# SCH_SrProj_v1_3.net
KiCad netlist of a schematic drawn in EasyEDA
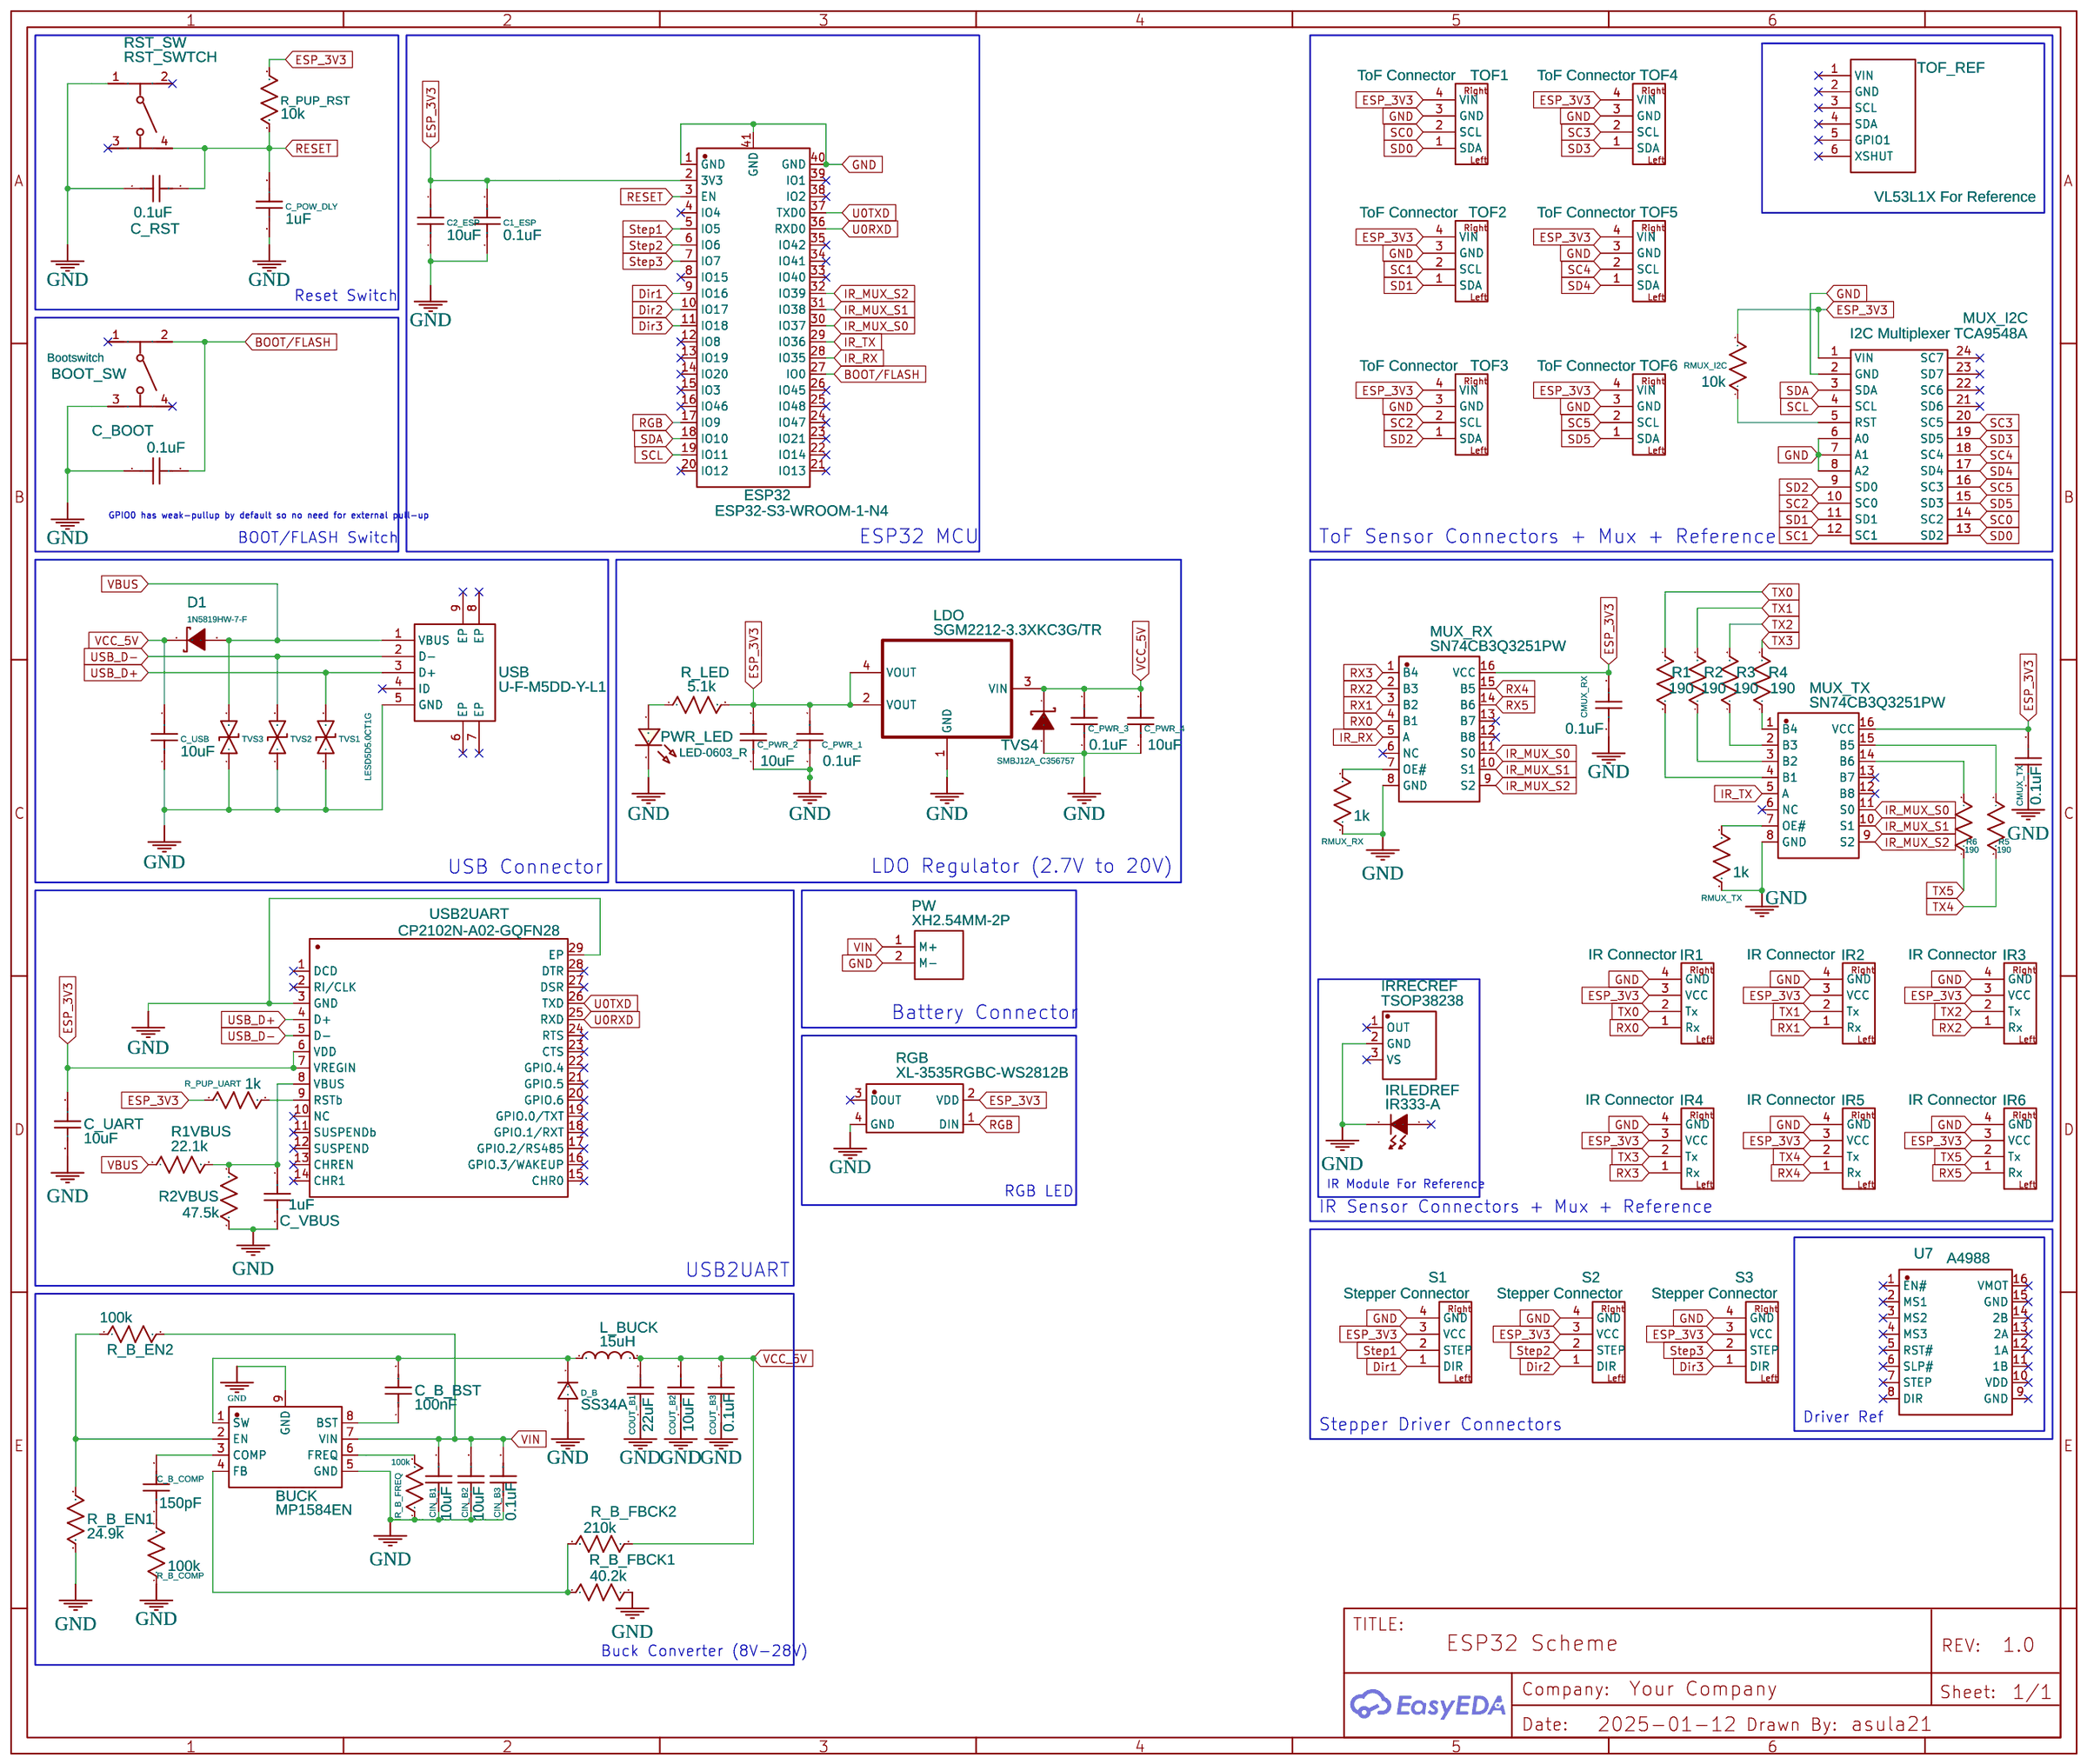
[diagram p0: schematic sheet]

(export (version "E")
  (design (tool "Eeschema 10.0.6"))
  (components
    (comp (ref "BOOT_SW")
      (value "Bootswitch")
      (fields
        (field (name "Manufacturer Part") "Switch,6*6*6Plastic head,260G, 0.25mm,Straight line")
        (field (name "Manufacturer") "BBJ")
      )
      (libsource (lib "") (part "Button-6x6x6mm_1"))
    )
    (comp (ref "BUCK") (value "MP1584EN") (libsource (lib "") (part "MP1584EN")))
    (comp (ref "C1_ESP") (value "0.1uF") (libsource (lib "") (part "C_0603_US")))
    (comp (ref "C2_ESP") (value "10uF") (libsource (lib "") (part "C_0603_US_14")))
    (comp (ref "CIN_B1") (value "10uF") (libsource (lib "") (part "C_0603_US_1")))
    (comp (ref "CIN_B2") (value "10uF") (libsource (lib "") (part "C_0603_US_1")))
    (comp (ref "CIN_B3") (value "0.1uF") (libsource (lib "") (part "C_0603_US_1")))
    (comp (ref "CMUX_RX") (value "0.1uF") (libsource (lib "") (part "C_0603_US_8")))
    (comp (ref "CMUX_TX") (value "0.1uF") (libsource (lib "") (part "C_0603_US_10")))
    (comp (ref "COUT_B1") (value "22uF") (libsource (lib "") (part "C_0603_US_3")))
    (comp (ref "COUT_B2") (value "10uF") (libsource (lib "") (part "C_0603_US_3")))
    (comp (ref "COUT_B3") (value "0.1uF") (libsource (lib "") (part "C_0603_US_3")))
    (comp (ref "C_BOOT") (value "0.1uF") (libsource (lib "") (part "C_0603_US_9")))
    (comp (ref "C_B_BST") (value "100nF") (libsource (lib "") (part "C_0603_US_12")))
    (comp (ref "C_B_COMP") (value "150pF") (libsource (lib "") (part "C_0603_US_13")))
    (comp (ref "C_POW_DLY") (value "1uF") (libsource (lib "") (part "C_0603_US_2")))
    (comp (ref "C_PWR_1") (value "0.1uF") (libsource (lib "") (part "C_0603_US_6")))
    (comp (ref "C_PWR_2") (value "10uF") (libsource (lib "") (part "C_0603_US_6")))
    (comp (ref "C_PWR_3") (value "0.1uF") (libsource (lib "") (part "C_0603_US_6")))
    (comp (ref "C_PWR_4") (value "10uF") (libsource (lib "") (part "C_0603_US_6")))
    (comp (ref "C_RST") (value "0.1uF") (libsource (lib "") (part "C_0603_US_7")))
    (comp (ref "C_UART") (value "10uF") (libsource (lib "") (part "C_0603_US_4")))
    (comp (ref "C_USB") (value "10uF") (libsource (lib "") (part "C_0603_US_5")))
    (comp (ref "C_VBUS") (value "1uF") (libsource (lib "") (part "C_0603_US_11")))
    (comp (ref "D1")
      (value "1N5819HW-7-F")
      (fields (field (name "Manufacturer") "DIODES(美台)"))
      (libsource (lib "") (part "1N5819HW-7-F"))
    )
    (comp (ref "D_B")
      (value "SS34A")
      (fields (field (name "Manufacturer") "YANGJIE(扬杰)"))
      (libsource (lib "") (part "SS34A"))
    )
    (comp (ref "ESP32")
      (value "ESP32-S3-WROOM-1-N4")
      (fields (field (name "Manufacturer") "ESPRESSIF(乐鑫)"))
      (libsource (lib "") (part "ESP32-S3-WROOM-1-N4"))
    )
    (comp (ref "IR1") (value "IR Connector") (libsource (lib "") (part "MY XH2.54MM.4P_1")))
    (comp (ref "IR2") (value "IR Connector") (libsource (lib "") (part "MY XH2.54MM.4P_1")))
    (comp (ref "IR3") (value "IR Connector") (libsource (lib "") (part "MY XH2.54MM.4P_1")))
    (comp (ref "IR4") (value "IR Connector") (libsource (lib "") (part "MY XH2.54MM.4P_1")))
    (comp (ref "IR5") (value "IR Connector") (libsource (lib "") (part "MY XH2.54MM.4P_1")))
    (comp (ref "IR6") (value "IR Connector") (libsource (lib "") (part "MY XH2.54MM.4P_1")))
    (comp (ref "IRLEDREF")
      (value "IR333-A")
      (fields (field (name "Manufacturer") "EVERLIGHT(亿光)"))
      (libsource (lib "") (part "IR333-A"))
    )
    (comp (ref "IRRECREF")
      (value "TSOP38238")
      (fields (field (name "Manufacturer") "VISHAY(威世)"))
      (libsource (lib "") (part "TSOP38238"))
    )
    (comp (ref "LDO") (value "SGM2212-3.3XKC3G/TR") (libsource (lib "") (part "SGM2212-3.3XKC3G/TR")))
    (comp (ref "L_BUCK")
      (value "15uH")
      (fields (field (name "Manufacturer Part") "CYH127-4.7UH") (field (name "Manufacturer") "SHOU HAN(首韩)"))
      (libsource (lib "") (part "CYH127-4.7UH"))
    )
    (comp (ref "MUX_I2C")
      (value "I2C Multiplexer TCA9548A")
      (fields (field (name "Manufacturer Part") "IDSN-TCA9548A") (field (name "Manufacturer") "IDSN"))
      (libsource (lib "") (part "TCA9548A I2C MULTIPLEXER 8 CHANEL"))
    )
    (comp (ref "MUX_RX")
      (value "SN74CB3Q3251PW")
      (fields (field (name "Manufacturer") "TI(德州仪器)"))
      (libsource (lib "") (part "SN74CB3Q3251PW"))
    )
    (comp (ref "MUX_TX")
      (value "SN74CB3Q3251PW")
      (fields (field (name "Manufacturer") "TI(德州仪器)"))
      (libsource (lib "") (part "SN74CB3Q3251PW_1"))
    )
    (comp (ref "PW")
      (value "XH2.54MM-2P")
      (fields (field (name "Manufacturer Part") "Header P2 PH2.0 TUANLE"))
      (libsource (lib "") (part "PH2.0-2P"))
    )
    (comp (ref "PWR_LED")
      (value "LED-0603_R")
      (fields
        (field (name "Manufacturer Part") "19-217/R6C-AL1M2VY/3T")
        (field (name "Manufacturer") "EVERLIGHT(台湾亿光)")
      )
      (libsource (lib "") (part "LED-0603_R"))
    )
    (comp (ref "R1") (value "190") (libsource (lib "") (part "R_0805_US_1")))
    (comp (ref "R1VBUS") (value "22.1k") (libsource (lib "") (part "R_0603_US_8")))
    (comp (ref "R2") (value "190") (libsource (lib "") (part "R_0805_US")))
    (comp (ref "R2VBUS") (value "47.5k") (libsource (lib "") (part "R_0603_US_11")))
    (comp (ref "R3") (value "190") (libsource (lib "") (part "R_0805_US")))
    (comp (ref "R4") (value "190") (libsource (lib "") (part "R_0805_US")))
    (comp (ref "R5") (value "190") (libsource (lib "") (part "R_0805_US_1")))
    (comp (ref "R6") (value "190") (libsource (lib "") (part "R_0805_US")))
    (comp (ref "RGB")
      (value "XL-3535RGBC-WS2812B")
      (fields (field (name "Manufacturer") "XINGLIGHT(成兴光)"))
      (libsource (lib "") (part "XL-3535RGBC-WS2812B"))
    )
    (comp (ref "RMUX_I2C") (value "10k") (libsource (lib "") (part "R_0603_US_1")))
    (comp (ref "RMUX_RX") (value "1k") (libsource (lib "") (part "R_0603_US_2")))
    (comp (ref "RMUX_TX") (value "1k") (libsource (lib "") (part "R_0603_US_3")))
    (comp (ref "RST_SW")
      (value "RST_SWTCH")
      (fields
        (field (name "Manufacturer Part") "Switch,6*6*6Plastic head,260G, 0.25mm,Straight line")
        (field (name "Manufacturer") "BBJ")
      )
      (libsource (lib "") (part "Button-6x6x6mm"))
    )
    (comp (ref "R_B_COMP") (value "100k") (libsource (lib "") (part "R_0603_US_4")))
    (comp (ref "R_B_EN1") (value "24.9k") (libsource (lib "") (part "R_0603_US_9")))
    (comp (ref "R_B_EN2") (value "100k") (libsource (lib "") (part "R_0603_US_7")))
    (comp (ref "R_B_FBCK1") (value "40.2k") (libsource (lib "") (part "R_0603_US")))
    (comp (ref "R_B_FBCK2") (value "210k") (libsource (lib "") (part "R_0603_US_13")))
    (comp (ref "R_B_FREQ") (value "100k") (libsource (lib "") (part "R_0603_US_12")))
    (comp (ref "R_LED") (value "5.1k") (libsource (lib "") (part "R_0603_US_5")))
    (comp (ref "R_PUP_RST") (value "10k") (libsource (lib "") (part "R_0603_US_6")))
    (comp (ref "R_PUP_UART") (value "1k") (libsource (lib "") (part "R_0603_US_10")))
    (comp (ref "S1") (value "Stepper Connector") (libsource (lib "") (part "MY XH2.54MM.4P_2")))
    (comp (ref "S2") (value "Stepper Connector") (libsource (lib "") (part "MY XH2.54MM.4P_2")))
    (comp (ref "S3") (value "Stepper Connector") (libsource (lib "") (part "MY XH2.54MM.4P_2")))
    (comp (ref "TOF1") (value "ToF Connector") (libsource (lib "") (part "MY XH2.54MM.4P")))
    (comp (ref "TOF2") (value "ToF Connector") (libsource (lib "") (part "MY XH2.54MM.4P")))
    (comp (ref "TOF3") (value "ToF Connector") (libsource (lib "") (part "MY XH2.54MM.4P")))
    (comp (ref "TOF4") (value "ToF Connector") (libsource (lib "") (part "MY XH2.54MM.4P")))
    (comp (ref "TOF5") (value "ToF Connector") (libsource (lib "") (part "MY XH2.54MM.4P")))
    (comp (ref "TOF6") (value "ToF Connector") (libsource (lib "") (part "MY XH2.54MM.4P")))
    (comp (ref "TOF_REF")
      (value "VL53L1X For Reference")
      (fields (field (name "Manufacturer Part") "VL53L0X Time-of-Flight Distance Sensor VL53L0X"))
      (libsource (lib "") (part "VL53L1X_BREAKOUT"))
    )
    (comp (ref "TVS1")
      (value "LESD5D5.0CT1G")
      (fields (field (name "Manufacturer") "LRC(乐山无线电)"))
      (libsource (lib "") (part "LESD5D5.0CT1G"))
    )
    (comp (ref "TVS2")
      (value "LESD5D5.0CT1G")
      (fields (field (name "Manufacturer") "LRC(乐山无线电)"))
      (libsource (lib "") (part "LESD5D5.0CT1G"))
    )
    (comp (ref "TVS3")
      (value "LESD5D5.0CT1G")
      (fields (field (name "Manufacturer") "LRC(乐山无线电)"))
      (libsource (lib "") (part "LESD5D5.0CT1G"))
    )
    (comp (ref "TVS4")
      (value "SMBJ12A_C356757")
      (fields (field (name "Manufacturer Part") "SMBJ12A") (field (name "Manufacturer") "JJW(捷捷微)"))
      (libsource (lib "") (part "SMBJ12A_C356757"))
    )
    (comp (ref "U7") (value "A4988") (libsource (lib "") (part "A4988")))
    (comp (ref "USB")
      (value "U-F-M5DD-Y-L1")
      (fields (field (name "Manufacturer") "韩国韩荣"))
      (libsource (lib "") (part "U-F-M5DD-Y-L1"))
    )
    (comp (ref "USB2UART")
      (value "CP2102N-A02-GQFN28")
      (fields (field (name "Manufacturer") "SKYWORKS/SILICON LABS(芯科)"))
      (libsource (lib "") (part "CP2102N-A02-GQFN28"))
    )
  )
  (nets
    (net (code "1") (name "BOOT{slash}FLASH") (class "Default")
      (node (ref "BOOT_SW") (pin "2") (pinfunction "2_2") (pintype "unspecified"))
      (node (ref "C_BOOT") (pin "2") (pinfunction "2_2") (pintype "unspecified"))
      (node (ref "ESP32") (pin "27") (pinfunction "IO0_27") (pintype "unspecified"))
    )
    (net (code "2") (name "Dir1") (class "Default")
      (node (ref "ESP32") (pin "9") (pinfunction "IO16_9") (pintype "unspecified"))
      (node (ref "S1") (pin "1") (pinfunction "DIR_1") (pintype "unspecified"))
    )
    (net (code "3") (name "Dir2") (class "Default")
      (node (ref "ESP32") (pin "10") (pinfunction "IO17_10") (pintype "unspecified"))
      (node (ref "S2") (pin "1") (pinfunction "DIR_1") (pintype "unspecified"))
    )
    (net (code "4") (name "Dir3") (class "Default")
      (node (ref "ESP32") (pin "11") (pinfunction "IO18_11") (pintype "unspecified"))
      (node (ref "S3") (pin "1") (pinfunction "DIR_1") (pintype "unspecified"))
    )
    (net (code "5") (name "ESP_3V3") (class "Default")
      (node (ref "C1_ESP") (pin "2") (pinfunction "2_2") (pintype "unspecified"))
      (node (ref "C2_ESP") (pin "2") (pinfunction "2_2") (pintype "unspecified"))
      (node (ref "CMUX_RX") (pin "2") (pinfunction "2_2") (pintype "unspecified"))
      (node (ref "CMUX_TX") (pin "2") (pinfunction "2_2") (pintype "unspecified"))
      (node (ref "C_PWR_1") (pin "2") (pinfunction "2_2") (pintype "unspecified"))
      (node (ref "C_PWR_2") (pin "2") (pinfunction "2_2") (pintype "unspecified"))
      (node (ref "C_UART") (pin "2") (pinfunction "2_2") (pintype "unspecified"))
      (node (ref "ESP32") (pin "2") (pinfunction "3V3_2") (pintype "unspecified"))
      (node (ref "IR1") (pin "3") (pinfunction "VCC_3") (pintype "unspecified"))
      (node (ref "IR2") (pin "3") (pinfunction "VCC_3") (pintype "unspecified"))
      (node (ref "IR3") (pin "3") (pinfunction "VCC_3") (pintype "unspecified"))
      (node (ref "IR4") (pin "3") (pinfunction "VCC_3") (pintype "unspecified"))
      (node (ref "IR5") (pin "3") (pinfunction "VCC_3") (pintype "unspecified"))
      (node (ref "IR6") (pin "3") (pinfunction "VCC_3") (pintype "unspecified"))
      (node (ref "LDO") (pin "2") (pinfunction "VOUT_2") (pintype "unspecified"))
      (node (ref "LDO") (pin "4") (pinfunction "VOUT_4") (pintype "unspecified"))
      (node (ref "MUX_I2C") (pin "1") (pinfunction "VIN_1") (pintype "unspecified"))
      (node (ref "MUX_RX") (pin "16") (pinfunction "VCC_16") (pintype "unspecified"))
      (node (ref "MUX_TX") (pin "16") (pinfunction "VCC_16") (pintype "unspecified"))
      (node (ref "RGB") (pin "2") (pinfunction "VDD_2") (pintype "unspecified"))
      (node (ref "RMUX_I2C") (pin "2") (pinfunction "2_2") (pintype "unspecified"))
      (node (ref "R_LED") (pin "2") (pinfunction "2_2") (pintype "unspecified"))
      (node (ref "R_PUP_RST") (pin "2") (pinfunction "2_2") (pintype "unspecified"))
      (node (ref "R_PUP_UART") (pin "2") (pinfunction "2_2") (pintype "unspecified"))
      (node (ref "S1") (pin "3") (pinfunction "VCC_3") (pintype "unspecified"))
      (node (ref "S2") (pin "3") (pinfunction "VCC_3") (pintype "unspecified"))
      (node (ref "S3") (pin "3") (pinfunction "VCC_3") (pintype "unspecified"))
      (node (ref "TOF1") (pin "4") (pinfunction "VIN_4") (pintype "unspecified"))
      (node (ref "TOF2") (pin "4") (pinfunction "VIN_4") (pintype "unspecified"))
      (node (ref "TOF3") (pin "4") (pinfunction "VIN_4") (pintype "unspecified"))
      (node (ref "TOF4") (pin "4") (pinfunction "VIN_4") (pintype "unspecified"))
      (node (ref "TOF5") (pin "4") (pinfunction "VIN_4") (pintype "unspecified"))
      (node (ref "TOF6") (pin "4") (pinfunction "VIN_4") (pintype "unspecified"))
      (node (ref "USB2UART") (pin "6") (pinfunction "VDD_6") (pintype "unspecified"))
      (node (ref "USB2UART") (pin "7") (pinfunction "VREGIN_7") (pintype "unspecified"))
    )
    (net (code "6") (name "GND") (class "Default")
      (node (ref "BOOT_SW") (pin "3") (pinfunction "3_3") (pintype "unspecified"))
      (node (ref "BUCK") (pin "5") (pinfunction "GND_5") (pintype "unspecified"))
      (node (ref "BUCK") (pin "9") (pinfunction "GND_9") (pintype "unspecified"))
      (node (ref "C1_ESP") (pin "1") (pinfunction "1_1") (pintype "unspecified"))
      (node (ref "C2_ESP") (pin "1") (pinfunction "1_1") (pintype "unspecified"))
      (node (ref "CIN_B1") (pin "1") (pinfunction "1_1") (pintype "unspecified"))
      (node (ref "CIN_B2") (pin "1") (pinfunction "1_1") (pintype "unspecified"))
      (node (ref "CIN_B3") (pin "1") (pinfunction "1_1") (pintype "unspecified"))
      (node (ref "CMUX_RX") (pin "1") (pinfunction "1_1") (pintype "unspecified"))
      (node (ref "CMUX_TX") (pin "1") (pinfunction "1_1") (pintype "unspecified"))
      (node (ref "COUT_B1") (pin "1") (pinfunction "1_1") (pintype "unspecified"))
      (node (ref "COUT_B2") (pin "1") (pinfunction "1_1") (pintype "unspecified"))
      (node (ref "COUT_B3") (pin "1") (pinfunction "1_1") (pintype "unspecified"))
      (node (ref "C_BOOT") (pin "1") (pinfunction "1_1") (pintype "unspecified"))
      (node (ref "C_POW_DLY") (pin "1") (pinfunction "1_1") (pintype "unspecified"))
      (node (ref "C_PWR_1") (pin "1") (pinfunction "1_1") (pintype "unspecified"))
      (node (ref "C_PWR_2") (pin "1") (pinfunction "1_1") (pintype "unspecified"))
      (node (ref "C_PWR_3") (pin "1") (pinfunction "1_1") (pintype "unspecified"))
      (node (ref "C_PWR_4") (pin "1") (pinfunction "1_1") (pintype "unspecified"))
      (node (ref "C_RST") (pin "1") (pinfunction "1_1") (pintype "unspecified"))
      (node (ref "C_UART") (pin "1") (pinfunction "1_1") (pintype "unspecified"))
      (node (ref "C_USB") (pin "1") (pinfunction "1_1") (pintype "unspecified"))
      (node (ref "C_VBUS") (pin "2") (pinfunction "2_2") (pintype "unspecified"))
      (node (ref "D_B") (pin "2") (pinfunction "A_2") (pintype "unspecified"))
      (node (ref "ESP32") (pin "1") (pinfunction "GND_1") (pintype "unspecified"))
      (node (ref "ESP32") (pin "40") (pinfunction "GND_40") (pintype "unspecified"))
      (node (ref "ESP32") (pin "41") (pinfunction "GND_41") (pintype "unspecified"))
      (node (ref "IR1") (pin "4") (pinfunction "GND_4") (pintype "unspecified"))
      (node (ref "IR2") (pin "4") (pinfunction "GND_4") (pintype "unspecified"))
      (node (ref "IR3") (pin "4") (pinfunction "GND_4") (pintype "unspecified"))
      (node (ref "IR4") (pin "4") (pinfunction "GND_4") (pintype "unspecified"))
      (node (ref "IR5") (pin "4") (pinfunction "GND_4") (pintype "unspecified"))
      (node (ref "IR6") (pin "4") (pinfunction "GND_4") (pintype "unspecified"))
      (node (ref "IRLEDREF") (pin "2") (pinfunction "C_2") (pintype "input"))
      (node (ref "IRRECREF") (pin "2") (pinfunction "GND_2") (pintype "unspecified"))
      (node (ref "LDO") (pin "1") (pinfunction "GND_1") (pintype "unspecified"))
      (node (ref "MUX_I2C") (pin "2") (pinfunction "GND_2") (pintype "unspecified"))
      (node (ref "MUX_I2C") (pin "6") (pinfunction "A0_6") (pintype "unspecified"))
      (node (ref "MUX_I2C") (pin "7") (pinfunction "A1_7") (pintype "unspecified"))
      (node (ref "MUX_I2C") (pin "8") (pinfunction "A2_8") (pintype "unspecified"))
      (node (ref "MUX_RX") (pin "8") (pinfunction "GND_8") (pintype "unspecified"))
      (node (ref "MUX_TX") (pin "8") (pinfunction "GND_8") (pintype "unspecified"))
      (node (ref "PW") (pin "2") (pinfunction "M-_2") (pintype "unspecified"))
      (node (ref "PWR_LED") (pin "2") (pinfunction "2_2") (pintype "unspecified"))
      (node (ref "R2VBUS") (pin "1") (pinfunction "1_1") (pintype "unspecified"))
      (node (ref "RGB") (pin "4") (pinfunction "GND_4") (pintype "unspecified"))
      (node (ref "RMUX_RX") (pin "1") (pinfunction "1_1") (pintype "unspecified"))
      (node (ref "RMUX_TX") (pin "1") (pinfunction "1_1") (pintype "unspecified"))
      (node (ref "RST_SW") (pin "1") (pinfunction "1_1") (pintype "unspecified"))
      (node (ref "R_B_COMP") (pin "1") (pinfunction "1_1") (pintype "unspecified"))
      (node (ref "R_B_EN1") (pin "1") (pinfunction "1_1") (pintype "unspecified"))
      (node (ref "R_B_FBCK1") (pin "2") (pinfunction "2_2") (pintype "unspecified"))
      (node (ref "R_B_FREQ") (pin "1") (pinfunction "1_1") (pintype "unspecified"))
      (node (ref "S1") (pin "4") (pinfunction "GND_4") (pintype "unspecified"))
      (node (ref "S2") (pin "4") (pinfunction "GND_4") (pintype "unspecified"))
      (node (ref "S3") (pin "4") (pinfunction "GND_4") (pintype "unspecified"))
      (node (ref "TOF1") (pin "3") (pinfunction "GND_3") (pintype "unspecified"))
      (node (ref "TOF2") (pin "3") (pinfunction "GND_3") (pintype "unspecified"))
      (node (ref "TOF3") (pin "3") (pinfunction "GND_3") (pintype "unspecified"))
      (node (ref "TOF4") (pin "3") (pinfunction "GND_3") (pintype "unspecified"))
      (node (ref "TOF5") (pin "3") (pinfunction "GND_3") (pintype "unspecified"))
      (node (ref "TOF6") (pin "3") (pinfunction "GND_3") (pintype "unspecified"))
      (node (ref "TVS1") (pin "1") (pinfunction "1_1") (pintype "unspecified"))
      (node (ref "TVS2") (pin "1") (pinfunction "1_1") (pintype "unspecified"))
      (node (ref "TVS3") (pin "1") (pinfunction "1_1") (pintype "unspecified"))
      (node (ref "TVS4") (pin "2") (pinfunction "A_2") (pintype "unspecified"))
      (node (ref "USB") (pin "5") (pinfunction "GND_5") (pintype "unspecified"))
      (node (ref "USB2UART") (pin "29") (pinfunction "EP_29") (pintype "unspecified"))
      (node (ref "USB2UART") (pin "3") (pinfunction "GND_3") (pintype "unspecified"))
    )
    (net (code "7") (name "IR_MUX_S0") (class "Default")
      (node (ref "ESP32") (pin "30") (pinfunction "IO37_30") (pintype "unspecified"))
      (node (ref "MUX_RX") (pin "11") (pinfunction "S0_11") (pintype "unspecified"))
      (node (ref "MUX_TX") (pin "11") (pinfunction "S0_11") (pintype "unspecified"))
    )
    (net (code "8") (name "IR_MUX_S1") (class "Default")
      (node (ref "ESP32") (pin "31") (pinfunction "IO38_31") (pintype "unspecified"))
      (node (ref "MUX_RX") (pin "10") (pinfunction "S1_10") (pintype "unspecified"))
      (node (ref "MUX_TX") (pin "10") (pinfunction "S1_10") (pintype "unspecified"))
    )
    (net (code "9") (name "IR_MUX_S2") (class "Default")
      (node (ref "ESP32") (pin "32") (pinfunction "IO39_32") (pintype "unspecified"))
      (node (ref "MUX_RX") (pin "9") (pinfunction "S2_9") (pintype "unspecified"))
      (node (ref "MUX_TX") (pin "9") (pinfunction "S2_9") (pintype "unspecified"))
    )
    (net (code "10") (name "IR_RX") (class "Default")
      (node (ref "ESP32") (pin "28") (pinfunction "IO35_28") (pintype "unspecified"))
      (node (ref "MUX_RX") (pin "5") (pinfunction "A_5") (pintype "unspecified"))
    )
    (net (code "11") (name "IR_TX") (class "Default")
      (node (ref "ESP32") (pin "29") (pinfunction "IO36_29") (pintype "unspecified"))
      (node (ref "MUX_TX") (pin "5") (pinfunction "A_5") (pintype "unspecified"))
    )
    (net (code "12") (name "Net-(BUCK-BST)") (class "Default")
      (node (ref "BUCK") (pin "8") (pinfunction "BST_8") (pintype "unspecified"))
      (node (ref "C_B_BST") (pin "1") (pinfunction "1_1") (pintype "unspecified"))
    )
    (net (code "13") (name "Net-(BUCK-COMP)") (class "Default")
      (node (ref "BUCK") (pin "3") (pinfunction "COMP_3") (pintype "unspecified"))
      (node (ref "C_B_COMP") (pin "2") (pinfunction "2_2") (pintype "unspecified"))
    )
    (net (code "14") (name "Net-(BUCK-EN)") (class "Default")
      (node (ref "BUCK") (pin "2") (pinfunction "EN_2") (pintype "unspecified"))
      (node (ref "R_B_EN1") (pin "2") (pinfunction "2_2") (pintype "unspecified"))
      (node (ref "R_B_EN2") (pin "1") (pinfunction "1_1") (pintype "unspecified"))
    )
    (net (code "15") (name "Net-(BUCK-FB)") (class "Default")
      (node (ref "BUCK") (pin "4") (pinfunction "FB_4") (pintype "unspecified"))
      (node (ref "R_B_FBCK1") (pin "1") (pinfunction "1_1") (pintype "unspecified"))
      (node (ref "R_B_FBCK2") (pin "2") (pinfunction "2_2") (pintype "unspecified"))
    )
    (net (code "16") (name "Net-(BUCK-FREQ)") (class "Default")
      (node (ref "BUCK") (pin "6") (pinfunction "FREQ_6") (pintype "unspecified"))
      (node (ref "R_B_FREQ") (pin "2") (pinfunction "2_2") (pintype "unspecified"))
    )
    (net (code "17") (name "Net-(BUCK-SW)") (class "Default")
      (node (ref "BUCK") (pin "1") (pinfunction "SW_1") (pintype "unspecified"))
      (node (ref "C_B_BST") (pin "2") (pinfunction "2_2") (pintype "unspecified"))
      (node (ref "D_B") (pin "1") (pinfunction "C_1") (pintype "unspecified"))
      (node (ref "L_BUCK") (pin "1") (pinfunction "1_1") (pintype "unspecified"))
    )
    (net (code "18") (name "Net-(C_B_COMP-Pad1)") (class "Default")
      (node (ref "C_B_COMP") (pin "1") (pinfunction "1_1") (pintype "unspecified"))
      (node (ref "R_B_COMP") (pin "2") (pinfunction "2_2") (pintype "unspecified"))
    )
    (net (code "19") (name "Net-(MUX_I2C-RST)") (class "Default")
      (node (ref "MUX_I2C") (pin "5") (pinfunction "RST_5") (pintype "unspecified"))
      (node (ref "RMUX_I2C") (pin "1") (pinfunction "1_1") (pintype "unspecified"))
    )
    (net (code "20") (name "Net-(MUX_RX-OE#)") (class "Default")
      (node (ref "MUX_RX") (pin "7") (pinfunction "OE#_7") (pintype "unspecified"))
      (node (ref "RMUX_RX") (pin "2") (pinfunction "2_2") (pintype "unspecified"))
    )
    (net (code "21") (name "Net-(MUX_TX-B1)") (class "Default")
      (node (ref "MUX_TX") (pin "4") (pinfunction "B1_4") (pintype "unspecified"))
      (node (ref "R1") (pin "2") (pinfunction "2_2") (pintype "unspecified"))
    )
    (net (code "22") (name "Net-(MUX_TX-B2)") (class "Default")
      (node (ref "MUX_TX") (pin "3") (pinfunction "B2_3") (pintype "unspecified"))
      (node (ref "R2") (pin "1") (pinfunction "1_1") (pintype "unspecified"))
    )
    (net (code "23") (name "Net-(MUX_TX-B3)") (class "Default")
      (node (ref "MUX_TX") (pin "2") (pinfunction "B3_2") (pintype "unspecified"))
      (node (ref "R3") (pin "1") (pinfunction "1_1") (pintype "unspecified"))
    )
    (net (code "24") (name "Net-(MUX_TX-B4)") (class "Default")
      (node (ref "MUX_TX") (pin "1") (pinfunction "B4_1") (pintype "unspecified"))
      (node (ref "R4") (pin "1") (pinfunction "1_1") (pintype "unspecified"))
    )
    (net (code "25") (name "Net-(MUX_TX-B5)") (class "Default")
      (node (ref "MUX_TX") (pin "15") (pinfunction "B5_15") (pintype "unspecified"))
      (node (ref "R5") (pin "1") (pinfunction "1_1") (pintype "unspecified"))
    )
    (net (code "26") (name "Net-(MUX_TX-B6)") (class "Default")
      (node (ref "MUX_TX") (pin "14") (pinfunction "B6_14") (pintype "unspecified"))
      (node (ref "R6") (pin "2") (pinfunction "2_2") (pintype "unspecified"))
    )
    (net (code "27") (name "Net-(MUX_TX-OE#)") (class "Default")
      (node (ref "MUX_TX") (pin "7") (pinfunction "OE#_7") (pintype "unspecified"))
      (node (ref "RMUX_TX") (pin "2") (pinfunction "2_2") (pintype "unspecified"))
    )
    (net (code "28") (name "Net-(PWR_LED-Pad1)") (class "Default")
      (node (ref "PWR_LED") (pin "1") (pinfunction "1_1") (pintype "unspecified"))
      (node (ref "R_LED") (pin "1") (pinfunction "1_1") (pintype "unspecified"))
    )
    (net (code "29") (name "Net-(USB2UART-RSTb)") (class "Default")
      (node (ref "R_PUP_UART") (pin "1") (pinfunction "1_1") (pintype "unspecified"))
      (node (ref "USB2UART") (pin "9") (pinfunction "RSTb_9") (pintype "unspecified"))
    )
    (net (code "30") (name "Net-(USB2UART-VBUS)") (class "Default")
      (node (ref "C_VBUS") (pin "1") (pinfunction "1_1") (pintype "unspecified"))
      (node (ref "R1VBUS") (pin "2") (pinfunction "2_2") (pintype "unspecified"))
      (node (ref "R2VBUS") (pin "2") (pinfunction "2_2") (pintype "unspecified"))
      (node (ref "USB2UART") (pin "8") (pinfunction "VBUS_8") (pintype "unspecified"))
    )
    (net (code "31") (name "RESET") (class "Default")
      (node (ref "C_POW_DLY") (pin "2") (pinfunction "2_2") (pintype "unspecified"))
      (node (ref "C_RST") (pin "2") (pinfunction "2_2") (pintype "unspecified"))
      (node (ref "ESP32") (pin "3") (pinfunction "EN_3") (pintype "unspecified"))
      (node (ref "RST_SW") (pin "4") (pinfunction "4_4") (pintype "unspecified"))
      (node (ref "R_PUP_RST") (pin "1") (pinfunction "1_1") (pintype "unspecified"))
    )
    (net (code "32") (name "RGB") (class "Default")
      (node (ref "ESP32") (pin "17") (pinfunction "IO9_17") (pintype "unspecified"))
      (node (ref "RGB") (pin "1") (pinfunction "DIN_1") (pintype "unspecified"))
    )
    (net (code "33") (name "RX0") (class "Default")
      (node (ref "IR1") (pin "1") (pinfunction "Rx_1") (pintype "unspecified"))
      (node (ref "MUX_RX") (pin "4") (pinfunction "B1_4") (pintype "unspecified"))
    )
    (net (code "34") (name "RX1") (class "Default")
      (node (ref "IR2") (pin "1") (pinfunction "Rx_1") (pintype "unspecified"))
      (node (ref "MUX_RX") (pin "3") (pinfunction "B2_3") (pintype "unspecified"))
    )
    (net (code "35") (name "RX2") (class "Default")
      (node (ref "IR3") (pin "1") (pinfunction "Rx_1") (pintype "unspecified"))
      (node (ref "MUX_RX") (pin "2") (pinfunction "B3_2") (pintype "unspecified"))
    )
    (net (code "36") (name "RX3") (class "Default")
      (node (ref "IR4") (pin "1") (pinfunction "Rx_1") (pintype "unspecified"))
      (node (ref "MUX_RX") (pin "1") (pinfunction "B4_1") (pintype "unspecified"))
    )
    (net (code "37") (name "RX4") (class "Default")
      (node (ref "IR5") (pin "1") (pinfunction "Rx_1") (pintype "unspecified"))
      (node (ref "MUX_RX") (pin "15") (pinfunction "B5_15") (pintype "unspecified"))
    )
    (net (code "38") (name "RX5") (class "Default")
      (node (ref "IR6") (pin "1") (pinfunction "Rx_1") (pintype "unspecified"))
      (node (ref "MUX_RX") (pin "14") (pinfunction "B6_14") (pintype "unspecified"))
    )
    (net (code "39") (name "SC0") (class "Default")
      (node (ref "MUX_I2C") (pin "14") (pinfunction "SC2_14") (pintype "unspecified"))
      (node (ref "TOF1") (pin "2") (pinfunction "SCL_2") (pintype "unspecified"))
    )
    (net (code "40") (name "SC1") (class "Default")
      (node (ref "MUX_I2C") (pin "12") (pinfunction "SC1_12") (pintype "unspecified"))
      (node (ref "TOF2") (pin "2") (pinfunction "SCL_2") (pintype "unspecified"))
    )
    (net (code "41") (name "SC2") (class "Default")
      (node (ref "MUX_I2C") (pin "10") (pinfunction "SC0_10") (pintype "unspecified"))
      (node (ref "TOF3") (pin "2") (pinfunction "SCL_2") (pintype "unspecified"))
    )
    (net (code "42") (name "SC3") (class "Default")
      (node (ref "MUX_I2C") (pin "20") (pinfunction "SC5_20") (pintype "unspecified"))
      (node (ref "TOF4") (pin "2") (pinfunction "SCL_2") (pintype "unspecified"))
    )
    (net (code "43") (name "SC4") (class "Default")
      (node (ref "MUX_I2C") (pin "18") (pinfunction "SC4_18") (pintype "unspecified"))
      (node (ref "TOF5") (pin "2") (pinfunction "SCL_2") (pintype "unspecified"))
    )
    (net (code "44") (name "SC5") (class "Default")
      (node (ref "MUX_I2C") (pin "16") (pinfunction "SC3_16") (pintype "unspecified"))
      (node (ref "TOF6") (pin "2") (pinfunction "SCL_2") (pintype "unspecified"))
    )
    (net (code "45") (name "SCL") (class "Default")
      (node (ref "ESP32") (pin "19") (pinfunction "IO11_19") (pintype "unspecified"))
      (node (ref "MUX_I2C") (pin "4") (pinfunction "SCL_4") (pintype "unspecified"))
    )
    (net (code "46") (name "SD0") (class "Default")
      (node (ref "MUX_I2C") (pin "13") (pinfunction "SD2_13") (pintype "unspecified"))
      (node (ref "TOF1") (pin "1") (pinfunction "SDA_1") (pintype "unspecified"))
    )
    (net (code "47") (name "SD1") (class "Default")
      (node (ref "MUX_I2C") (pin "11") (pinfunction "SD1_11") (pintype "unspecified"))
      (node (ref "TOF2") (pin "1") (pinfunction "SDA_1") (pintype "unspecified"))
    )
    (net (code "48") (name "SD2") (class "Default")
      (node (ref "MUX_I2C") (pin "9") (pinfunction "SD0_9") (pintype "unspecified"))
      (node (ref "TOF3") (pin "1") (pinfunction "SDA_1") (pintype "unspecified"))
    )
    (net (code "49") (name "SD3") (class "Default")
      (node (ref "MUX_I2C") (pin "19") (pinfunction "SD5_19") (pintype "unspecified"))
      (node (ref "TOF4") (pin "1") (pinfunction "SDA_1") (pintype "unspecified"))
    )
    (net (code "50") (name "SD4") (class "Default")
      (node (ref "MUX_I2C") (pin "17") (pinfunction "SD4_17") (pintype "unspecified"))
      (node (ref "TOF5") (pin "1") (pinfunction "SDA_1") (pintype "unspecified"))
    )
    (net (code "51") (name "SD5") (class "Default")
      (node (ref "MUX_I2C") (pin "15") (pinfunction "SD3_15") (pintype "unspecified"))
      (node (ref "TOF6") (pin "1") (pinfunction "SDA_1") (pintype "unspecified"))
    )
    (net (code "52") (name "SDA") (class "Default")
      (node (ref "ESP32") (pin "18") (pinfunction "IO10_18") (pintype "unspecified"))
      (node (ref "MUX_I2C") (pin "3") (pinfunction "SDA_3") (pintype "unspecified"))
    )
    (net (code "53") (name "Step1") (class "Default")
      (node (ref "ESP32") (pin "5") (pinfunction "IO5_5") (pintype "unspecified"))
      (node (ref "S1") (pin "2") (pinfunction "STEP_2") (pintype "unspecified"))
    )
    (net (code "54") (name "Step2") (class "Default")
      (node (ref "ESP32") (pin "6") (pinfunction "IO6_6") (pintype "unspecified"))
      (node (ref "S2") (pin "2") (pinfunction "STEP_2") (pintype "unspecified"))
    )
    (net (code "55") (name "Step3") (class "Default")
      (node (ref "ESP32") (pin "7") (pinfunction "IO7_7") (pintype "unspecified"))
      (node (ref "S3") (pin "2") (pinfunction "STEP_2") (pintype "unspecified"))
    )
    (net (code "56") (name "TX0") (class "Default")
      (node (ref "IR1") (pin "2") (pinfunction "Tx_2") (pintype "unspecified"))
      (node (ref "R1") (pin "1") (pinfunction "1_1") (pintype "unspecified"))
    )
    (net (code "57") (name "TX1") (class "Default")
      (node (ref "IR2") (pin "2") (pinfunction "Tx_2") (pintype "unspecified"))
      (node (ref "R2") (pin "2") (pinfunction "2_2") (pintype "unspecified"))
    )
    (net (code "58") (name "TX2") (class "Default")
      (node (ref "IR3") (pin "2") (pinfunction "Tx_2") (pintype "unspecified"))
      (node (ref "R3") (pin "2") (pinfunction "2_2") (pintype "unspecified"))
    )
    (net (code "59") (name "TX3") (class "Default")
      (node (ref "IR4") (pin "2") (pinfunction "Tx_2") (pintype "unspecified"))
      (node (ref "R4") (pin "2") (pinfunction "2_2") (pintype "unspecified"))
    )
    (net (code "60") (name "TX4") (class "Default")
      (node (ref "IR5") (pin "2") (pinfunction "Tx_2") (pintype "unspecified"))
      (node (ref "R5") (pin "2") (pinfunction "2_2") (pintype "unspecified"))
    )
    (net (code "61") (name "TX5") (class "Default")
      (node (ref "IR6") (pin "2") (pinfunction "Tx_2") (pintype "unspecified"))
      (node (ref "R6") (pin "1") (pinfunction "1_1") (pintype "unspecified"))
    )
    (net (code "62") (name "U0RXD") (class "Default")
      (node (ref "ESP32") (pin "36") (pinfunction "RXD0_36") (pintype "unspecified"))
      (node (ref "USB2UART") (pin "25") (pinfunction "RXD_25") (pintype "unspecified"))
    )
    (net (code "63") (name "U0TXD") (class "Default")
      (node (ref "ESP32") (pin "37") (pinfunction "TXD0_37") (pintype "unspecified"))
      (node (ref "USB2UART") (pin "26") (pinfunction "TXD_26") (pintype "unspecified"))
    )
    (net (code "64") (name "USB_D+") (class "Default")
      (node (ref "TVS1") (pin "2") (pinfunction "2_2") (pintype "unspecified"))
      (node (ref "USB") (pin "3") (pinfunction "D+_3") (pintype "unspecified"))
      (node (ref "USB2UART") (pin "4") (pinfunction "D+_4") (pintype "unspecified"))
    )
    (net (code "65") (name "USB_D-") (class "Default")
      (node (ref "TVS2") (pin "2") (pinfunction "2_2") (pintype "unspecified"))
      (node (ref "USB") (pin "2") (pinfunction "D-_2") (pintype "unspecified"))
      (node (ref "USB2UART") (pin "5") (pinfunction "D-_5") (pintype "unspecified"))
    )
    (net (code "66") (name "VBUS") (class "Default")
      (node (ref "D1") (pin "2") (pinfunction "A_2") (pintype "unspecified"))
      (node (ref "R1VBUS") (pin "1") (pinfunction "1_1") (pintype "unspecified"))
      (node (ref "TVS3") (pin "2") (pinfunction "2_2") (pintype "unspecified"))
      (node (ref "USB") (pin "1") (pinfunction "VBUS_1") (pintype "unspecified"))
    )
    (net (code "67") (name "VCC_5V") (class "Default")
      (node (ref "COUT_B1") (pin "2") (pinfunction "2_2") (pintype "unspecified"))
      (node (ref "COUT_B2") (pin "2") (pinfunction "2_2") (pintype "unspecified"))
      (node (ref "COUT_B3") (pin "2") (pinfunction "2_2") (pintype "unspecified"))
      (node (ref "C_PWR_3") (pin "2") (pinfunction "2_2") (pintype "unspecified"))
      (node (ref "C_PWR_4") (pin "2") (pinfunction "2_2") (pintype "unspecified"))
      (node (ref "C_USB") (pin "2") (pinfunction "2_2") (pintype "unspecified"))
      (node (ref "D1") (pin "1") (pinfunction "K_1") (pintype "unspecified"))
      (node (ref "LDO") (pin "3") (pinfunction "VIN_3") (pintype "unspecified"))
      (node (ref "L_BUCK") (pin "2") (pinfunction "2_2") (pintype "unspecified"))
      (node (ref "R_B_FBCK2") (pin "1") (pinfunction "1_1") (pintype "unspecified"))
      (node (ref "TVS4") (pin "1") (pinfunction "K_1") (pintype "unspecified"))
    )
    (net (code "68") (name "VIN") (class "Default")
      (node (ref "BUCK") (pin "7") (pinfunction "VIN_7") (pintype "unspecified"))
      (node (ref "CIN_B1") (pin "2") (pinfunction "2_2") (pintype "unspecified"))
      (node (ref "CIN_B2") (pin "2") (pinfunction "2_2") (pintype "unspecified"))
      (node (ref "CIN_B3") (pin "2") (pinfunction "2_2") (pintype "unspecified"))
      (node (ref "PW") (pin "1") (pinfunction "M+_1") (pintype "unspecified"))
      (node (ref "R_B_EN2") (pin "2") (pinfunction "2_2") (pintype "unspecified"))
    )
    (net (code "69") (name "unconnected-(BOOT_SW-Pad1)") (class "Default")
      (node (ref "BOOT_SW") (pin "1") (pinfunction "1_1") (pintype "unspecified+no_connect"))
    )
    (net (code "70") (name "unconnected-(BOOT_SW-Pad4)") (class "Default")
      (node (ref "BOOT_SW") (pin "4") (pinfunction "4_4") (pintype "unspecified+no_connect"))
    )
    (net (code "71") (name "unconnected-(ESP32-IO1-Pad39)") (class "Default")
      (node (ref "ESP32") (pin "39") (pinfunction "IO1_39") (pintype "unspecified+no_connect"))
    )
    (net (code "72") (name "unconnected-(ESP32-IO2-Pad38)") (class "Default")
      (node (ref "ESP32") (pin "38") (pinfunction "IO2_38") (pintype "unspecified+no_connect"))
    )
    (net (code "73") (name "unconnected-(ESP32-IO3-Pad15)") (class "Default")
      (node (ref "ESP32") (pin "15") (pinfunction "IO3_15") (pintype "unspecified+no_connect"))
    )
    (net (code "74") (name "unconnected-(ESP32-IO4-Pad4)") (class "Default")
      (node (ref "ESP32") (pin "4") (pinfunction "IO4_4") (pintype "unspecified+no_connect"))
    )
    (net (code "75") (name "unconnected-(ESP32-IO8-Pad12)") (class "Default")
      (node (ref "ESP32") (pin "12") (pinfunction "IO8_12") (pintype "unspecified+no_connect"))
    )
    (net (code "76") (name "unconnected-(ESP32-IO12-Pad20)") (class "Default")
      (node (ref "ESP32") (pin "20") (pinfunction "IO12_20") (pintype "unspecified+no_connect"))
    )
    (net (code "77") (name "unconnected-(ESP32-IO13-Pad21)") (class "Default")
      (node (ref "ESP32") (pin "21") (pinfunction "IO13_21") (pintype "unspecified+no_connect"))
    )
    (net (code "78") (name "unconnected-(ESP32-IO14-Pad22)") (class "Default")
      (node (ref "ESP32") (pin "22") (pinfunction "IO14_22") (pintype "unspecified+no_connect"))
    )
    (net (code "79") (name "unconnected-(ESP32-IO15-Pad8)") (class "Default")
      (node (ref "ESP32") (pin "8") (pinfunction "IO15_8") (pintype "unspecified+no_connect"))
    )
    (net (code "80") (name "unconnected-(ESP32-IO19-Pad13)") (class "Default")
      (node (ref "ESP32") (pin "13") (pinfunction "IO19_13") (pintype "unspecified+no_connect"))
    )
    (net (code "81") (name "unconnected-(ESP32-IO20-Pad14)") (class "Default")
      (node (ref "ESP32") (pin "14") (pinfunction "IO20_14") (pintype "unspecified+no_connect"))
    )
    (net (code "82") (name "unconnected-(ESP32-IO21-Pad23)") (class "Default")
      (node (ref "ESP32") (pin "23") (pinfunction "IO21_23") (pintype "unspecified+no_connect"))
    )
    (net (code "83") (name "unconnected-(ESP32-IO40-Pad33)") (class "Default")
      (node (ref "ESP32") (pin "33") (pinfunction "IO40_33") (pintype "unspecified+no_connect"))
    )
    (net (code "84") (name "unconnected-(ESP32-IO41-Pad34)") (class "Default")
      (node (ref "ESP32") (pin "34") (pinfunction "IO41_34") (pintype "unspecified+no_connect"))
    )
    (net (code "85") (name "unconnected-(ESP32-IO42-Pad35)") (class "Default")
      (node (ref "ESP32") (pin "35") (pinfunction "IO42_35") (pintype "unspecified+no_connect"))
    )
    (net (code "86") (name "unconnected-(ESP32-IO45-Pad26)") (class "Default")
      (node (ref "ESP32") (pin "26") (pinfunction "IO45_26") (pintype "unspecified+no_connect"))
    )
    (net (code "87") (name "unconnected-(ESP32-IO46-Pad16)") (class "Default")
      (node (ref "ESP32") (pin "16") (pinfunction "IO46_16") (pintype "unspecified+no_connect"))
    )
    (net (code "88") (name "unconnected-(ESP32-IO47-Pad24)") (class "Default")
      (node (ref "ESP32") (pin "24") (pinfunction "IO47_24") (pintype "unspecified+no_connect"))
    )
    (net (code "89") (name "unconnected-(ESP32-IO48-Pad25)") (class "Default")
      (node (ref "ESP32") (pin "25") (pinfunction "IO48_25") (pintype "unspecified+no_connect"))
    )
    (net (code "90") (name "unconnected-(IRLEDREF-A-Pad1)") (class "Default")
      (node (ref "IRLEDREF") (pin "1") (pinfunction "A_1") (pintype "input+no_connect"))
    )
    (net (code "91") (name "unconnected-(IRRECREF-OUT-Pad1)") (class "Default")
      (node (ref "IRRECREF") (pin "1") (pinfunction "OUT_1") (pintype "unspecified+no_connect"))
    )
    (net (code "92") (name "unconnected-(IRRECREF-VS-Pad3)") (class "Default")
      (node (ref "IRRECREF") (pin "3") (pinfunction "VS_3") (pintype "unspecified+no_connect"))
    )
    (net (code "93") (name "unconnected-(MUX_I2C-SC6-Pad22)") (class "Default")
      (node (ref "MUX_I2C") (pin "22") (pinfunction "SC6_22") (pintype "unspecified+no_connect"))
    )
    (net (code "94") (name "unconnected-(MUX_I2C-SC7-Pad24)") (class "Default")
      (node (ref "MUX_I2C") (pin "24") (pinfunction "SC7_24") (pintype "unspecified+no_connect"))
    )
    (net (code "95") (name "unconnected-(MUX_I2C-SD6-Pad21)") (class "Default")
      (node (ref "MUX_I2C") (pin "21") (pinfunction "SD6_21") (pintype "unspecified+no_connect"))
    )
    (net (code "96") (name "unconnected-(MUX_I2C-SD7-Pad23)") (class "Default")
      (node (ref "MUX_I2C") (pin "23") (pinfunction "SD7_23") (pintype "unspecified+no_connect"))
    )
    (net (code "97") (name "unconnected-(MUX_RX-B7-Pad13)") (class "Default")
      (node (ref "MUX_RX") (pin "13") (pinfunction "B7_13") (pintype "unspecified+no_connect"))
    )
    (net (code "98") (name "unconnected-(MUX_RX-B8-Pad12)") (class "Default")
      (node (ref "MUX_RX") (pin "12") (pinfunction "B8_12") (pintype "unspecified+no_connect"))
    )
    (net (code "99") (name "unconnected-(MUX_RX-NC-Pad6)") (class "Default")
      (node (ref "MUX_RX") (pin "6") (pinfunction "NC_6") (pintype "unspecified+no_connect"))
    )
    (net (code "100") (name "unconnected-(MUX_TX-B7-Pad13)") (class "Default")
      (node (ref "MUX_TX") (pin "13") (pinfunction "B7_13") (pintype "unspecified+no_connect"))
    )
    (net (code "101") (name "unconnected-(MUX_TX-B8-Pad12)") (class "Default")
      (node (ref "MUX_TX") (pin "12") (pinfunction "B8_12") (pintype "unspecified+no_connect"))
    )
    (net (code "102") (name "unconnected-(MUX_TX-NC-Pad6)") (class "Default")
      (node (ref "MUX_TX") (pin "6") (pinfunction "NC_6") (pintype "unspecified+no_connect"))
    )
    (net (code "103") (name "unconnected-(RGB-DOUT-Pad3)") (class "Default")
      (node (ref "RGB") (pin "3") (pinfunction "DOUT_3") (pintype "unspecified+no_connect"))
    )
    (net (code "104") (name "unconnected-(RST_SW-Pad2)") (class "Default")
      (node (ref "RST_SW") (pin "2") (pinfunction "2_2") (pintype "unspecified+no_connect"))
    )
    (net (code "105") (name "unconnected-(RST_SW-Pad3)") (class "Default")
      (node (ref "RST_SW") (pin "3") (pinfunction "3_3") (pintype "unspecified+no_connect"))
    )
    (net (code "106") (name "unconnected-(TOF_REF-GND-Pad2)") (class "Default")
      (node (ref "TOF_REF") (pin "2") (pinfunction "GND_2") (pintype "unspecified+no_connect"))
    )
    (net (code "107") (name "unconnected-(TOF_REF-GPIO1-Pad5)") (class "Default")
      (node (ref "TOF_REF") (pin "5") (pinfunction "GPIO1_5") (pintype "unspecified+no_connect"))
    )
    (net (code "108") (name "unconnected-(TOF_REF-SCL-Pad3)") (class "Default")
      (node (ref "TOF_REF") (pin "3") (pinfunction "SCL_3") (pintype "unspecified+no_connect"))
    )
    (net (code "109") (name "unconnected-(TOF_REF-SDA-Pad4)") (class "Default")
      (node (ref "TOF_REF") (pin "4") (pinfunction "SDA_4") (pintype "unspecified+no_connect"))
    )
    (net (code "110") (name "unconnected-(TOF_REF-VIN-Pad1)") (class "Default")
      (node (ref "TOF_REF") (pin "1") (pinfunction "VIN_1") (pintype "unspecified+no_connect"))
    )
    (net (code "111") (name "unconnected-(TOF_REF-XSHUT-Pad6)") (class "Default")
      (node (ref "TOF_REF") (pin "6") (pinfunction "XSHUT_6") (pintype "unspecified+no_connect"))
    )
    (net (code "112") (name "unconnected-(U7-1A-Pad12)") (class "Default")
      (node (ref "U7") (pin "12") (pinfunction "1A_12") (pintype "unspecified+no_connect"))
    )
    (net (code "113") (name "unconnected-(U7-1B-Pad11)") (class "Default")
      (node (ref "U7") (pin "11") (pinfunction "1B_11") (pintype "unspecified+no_connect"))
    )
    (net (code "114") (name "unconnected-(U7-2A-Pad13)") (class "Default")
      (node (ref "U7") (pin "13") (pinfunction "2A_13") (pintype "unspecified+no_connect"))
    )
    (net (code "115") (name "unconnected-(U7-2B-Pad14)") (class "Default")
      (node (ref "U7") (pin "14") (pinfunction "2B_14") (pintype "unspecified+no_connect"))
    )
    (net (code "116") (name "unconnected-(U7-DIR-Pad8)") (class "Default")
      (node (ref "U7") (pin "8") (pinfunction "DIR_8") (pintype "unspecified+no_connect"))
    )
    (net (code "117") (name "unconnected-(U7-EN#-Pad1)") (class "Default")
      (node (ref "U7") (pin "1") (pinfunction "EN#_1") (pintype "unspecified+no_connect"))
    )
    (net (code "118") (name "unconnected-(U7-GND-Pad9)") (class "Default")
      (node (ref "U7") (pin "9") (pinfunction "GND_9") (pintype "unspecified+no_connect"))
    )
    (net (code "119") (name "unconnected-(U7-GND-Pad15)") (class "Default")
      (node (ref "U7") (pin "15") (pinfunction "GND_15") (pintype "unspecified+no_connect"))
    )
    (net (code "120") (name "unconnected-(U7-MS1-Pad2)") (class "Default")
      (node (ref "U7") (pin "2") (pinfunction "MS1_2") (pintype "unspecified+no_connect"))
    )
    (net (code "121") (name "unconnected-(U7-MS2-Pad3)") (class "Default")
      (node (ref "U7") (pin "3") (pinfunction "MS2_3") (pintype "unspecified+no_connect"))
    )
    (net (code "122") (name "unconnected-(U7-MS3-Pad4)") (class "Default")
      (node (ref "U7") (pin "4") (pinfunction "MS3_4") (pintype "unspecified+no_connect"))
    )
    (net (code "123") (name "unconnected-(U7-RST#-Pad5)") (class "Default")
      (node (ref "U7") (pin "5") (pinfunction "RST#_5") (pintype "unspecified+no_connect"))
    )
    (net (code "124") (name "unconnected-(U7-SLP#-Pad6)") (class "Default")
      (node (ref "U7") (pin "6") (pinfunction "SLP#_6") (pintype "unspecified+no_connect"))
    )
    (net (code "125") (name "unconnected-(U7-STEP-Pad7)") (class "Default")
      (node (ref "U7") (pin "7") (pinfunction "STEP_7") (pintype "unspecified+no_connect"))
    )
    (net (code "126") (name "unconnected-(U7-VDD-Pad10)") (class "Default")
      (node (ref "U7") (pin "10") (pinfunction "VDD_10") (pintype "unspecified+no_connect"))
    )
    (net (code "127") (name "unconnected-(U7-VMOT-Pad16)") (class "Default")
      (node (ref "U7") (pin "16") (pinfunction "VMOT_16") (pintype "unspecified+no_connect"))
    )
    (net (code "128") (name "unconnected-(USB-EP-Pad6)") (class "Default")
      (node (ref "USB") (pin "6") (pinfunction "EP_6") (pintype "unspecified+no_connect"))
    )
    (net (code "129") (name "unconnected-(USB-EP-Pad7)") (class "Default")
      (node (ref "USB") (pin "7") (pinfunction "EP_7") (pintype "unspecified+no_connect"))
    )
    (net (code "130") (name "unconnected-(USB-EP-Pad8)") (class "Default")
      (node (ref "USB") (pin "8") (pinfunction "EP_8") (pintype "unspecified+no_connect"))
    )
    (net (code "131") (name "unconnected-(USB-EP-Pad9)") (class "Default")
      (node (ref "USB") (pin "9") (pinfunction "EP_9") (pintype "unspecified+no_connect"))
    )
    (net (code "132") (name "unconnected-(USB-ID-Pad4)") (class "Default")
      (node (ref "USB") (pin "4") (pinfunction "ID_4") (pintype "unspecified+no_connect"))
    )
    (net (code "133") (name "unconnected-(USB2UART-CHR0-Pad15)") (class "Default")
      (node (ref "USB2UART") (pin "15") (pinfunction "CHR0_15") (pintype "unspecified+no_connect"))
    )
    (net (code "134") (name "unconnected-(USB2UART-CHR1-Pad14)") (class "Default")
      (node (ref "USB2UART") (pin "14") (pinfunction "CHR1_14") (pintype "unspecified+no_connect"))
    )
    (net (code "135") (name "unconnected-(USB2UART-CHREN-Pad13)") (class "Default")
      (node (ref "USB2UART") (pin "13") (pinfunction "CHREN_13") (pintype "unspecified+no_connect"))
    )
    (net (code "136") (name "unconnected-(USB2UART-CTS-Pad23)") (class "Default")
      (node (ref "USB2UART") (pin "23") (pinfunction "CTS_23") (pintype "unspecified+no_connect"))
    )
    (net (code "137") (name "unconnected-(USB2UART-DCD-Pad1)") (class "Default")
      (node (ref "USB2UART") (pin "1") (pinfunction "DCD_1") (pintype "unspecified+no_connect"))
    )
    (net (code "138") (name "unconnected-(USB2UART-DSR-Pad27)") (class "Default")
      (node (ref "USB2UART") (pin "27") (pinfunction "DSR_27") (pintype "unspecified+no_connect"))
    )
    (net (code "139") (name "unconnected-(USB2UART-DTR-Pad28)") (class "Default")
      (node (ref "USB2UART") (pin "28") (pinfunction "DTR_28") (pintype "unspecified+no_connect"))
    )
    (net (code "140") (name "unconnected-(USB2UART-GPIO.0{slash}TXT-Pad19)") (class "Default")
      (node (ref "USB2UART") (pin "19") (pinfunction "GPIO.0/TXT_19") (pintype "unspecified+no_connect"))
    )
    (net (code "141") (name "unconnected-(USB2UART-GPIO.1{slash}RXT-Pad18)") (class "Default")
      (node (ref "USB2UART") (pin "18") (pinfunction "GPIO.1/RXT_18") (pintype "unspecified+no_connect"))
    )
    (net (code "142") (name "unconnected-(USB2UART-GPIO.2{slash}RS485-Pad17)") (class "Default")
      (node (ref "USB2UART") (pin "17") (pinfunction "GPIO.2/RS485_17") (pintype "unspecified+no_connect"))
    )
    (net (code "143") (name "unconnected-(USB2UART-GPIO.3{slash}WAKEUP-Pad16)") (class "Default")
      (node (ref "USB2UART") (pin "16") (pinfunction "GPIO.3/WAKEUP_16") (pintype "unspecified+no_connect"))
    )
    (net (code "144") (name "unconnected-(USB2UART-GPIO.4-Pad22)") (class "Default")
      (node (ref "USB2UART") (pin "22") (pinfunction "GPIO.4_22") (pintype "unspecified+no_connect"))
    )
    (net (code "145") (name "unconnected-(USB2UART-GPIO.5-Pad21)") (class "Default")
      (node (ref "USB2UART") (pin "21") (pinfunction "GPIO.5_21") (pintype "unspecified+no_connect"))
    )
    (net (code "146") (name "unconnected-(USB2UART-GPIO.6-Pad20)") (class "Default")
      (node (ref "USB2UART") (pin "20") (pinfunction "GPIO.6_20") (pintype "unspecified+no_connect"))
    )
    (net (code "147") (name "unconnected-(USB2UART-NC-Pad10)") (class "Default")
      (node (ref "USB2UART") (pin "10") (pinfunction "NC_10") (pintype "unspecified+no_connect"))
    )
    (net (code "148") (name "unconnected-(USB2UART-RI{slash}CLK-Pad2)") (class "Default")
      (node (ref "USB2UART") (pin "2") (pinfunction "RI/CLK_2") (pintype "unspecified+no_connect"))
    )
    (net (code "149") (name "unconnected-(USB2UART-RTS-Pad24)") (class "Default")
      (node (ref "USB2UART") (pin "24") (pinfunction "RTS_24") (pintype "unspecified+no_connect"))
    )
    (net (code "150") (name "unconnected-(USB2UART-SUSPEND-Pad12)") (class "Default")
      (node (ref "USB2UART") (pin "12") (pinfunction "SUSPEND_12") (pintype "unspecified+no_connect"))
    )
    (net (code "151") (name "unconnected-(USB2UART-SUSPENDb-Pad11)") (class "Default")
      (node (ref "USB2UART") (pin "11") (pinfunction "SUSPENDb_11") (pintype "unspecified+no_connect"))
    )
  )
)
